# OSO-MISC-21-005_SAML22_Feather.net
KiCad netlist of a schematic drawn in EAGLE
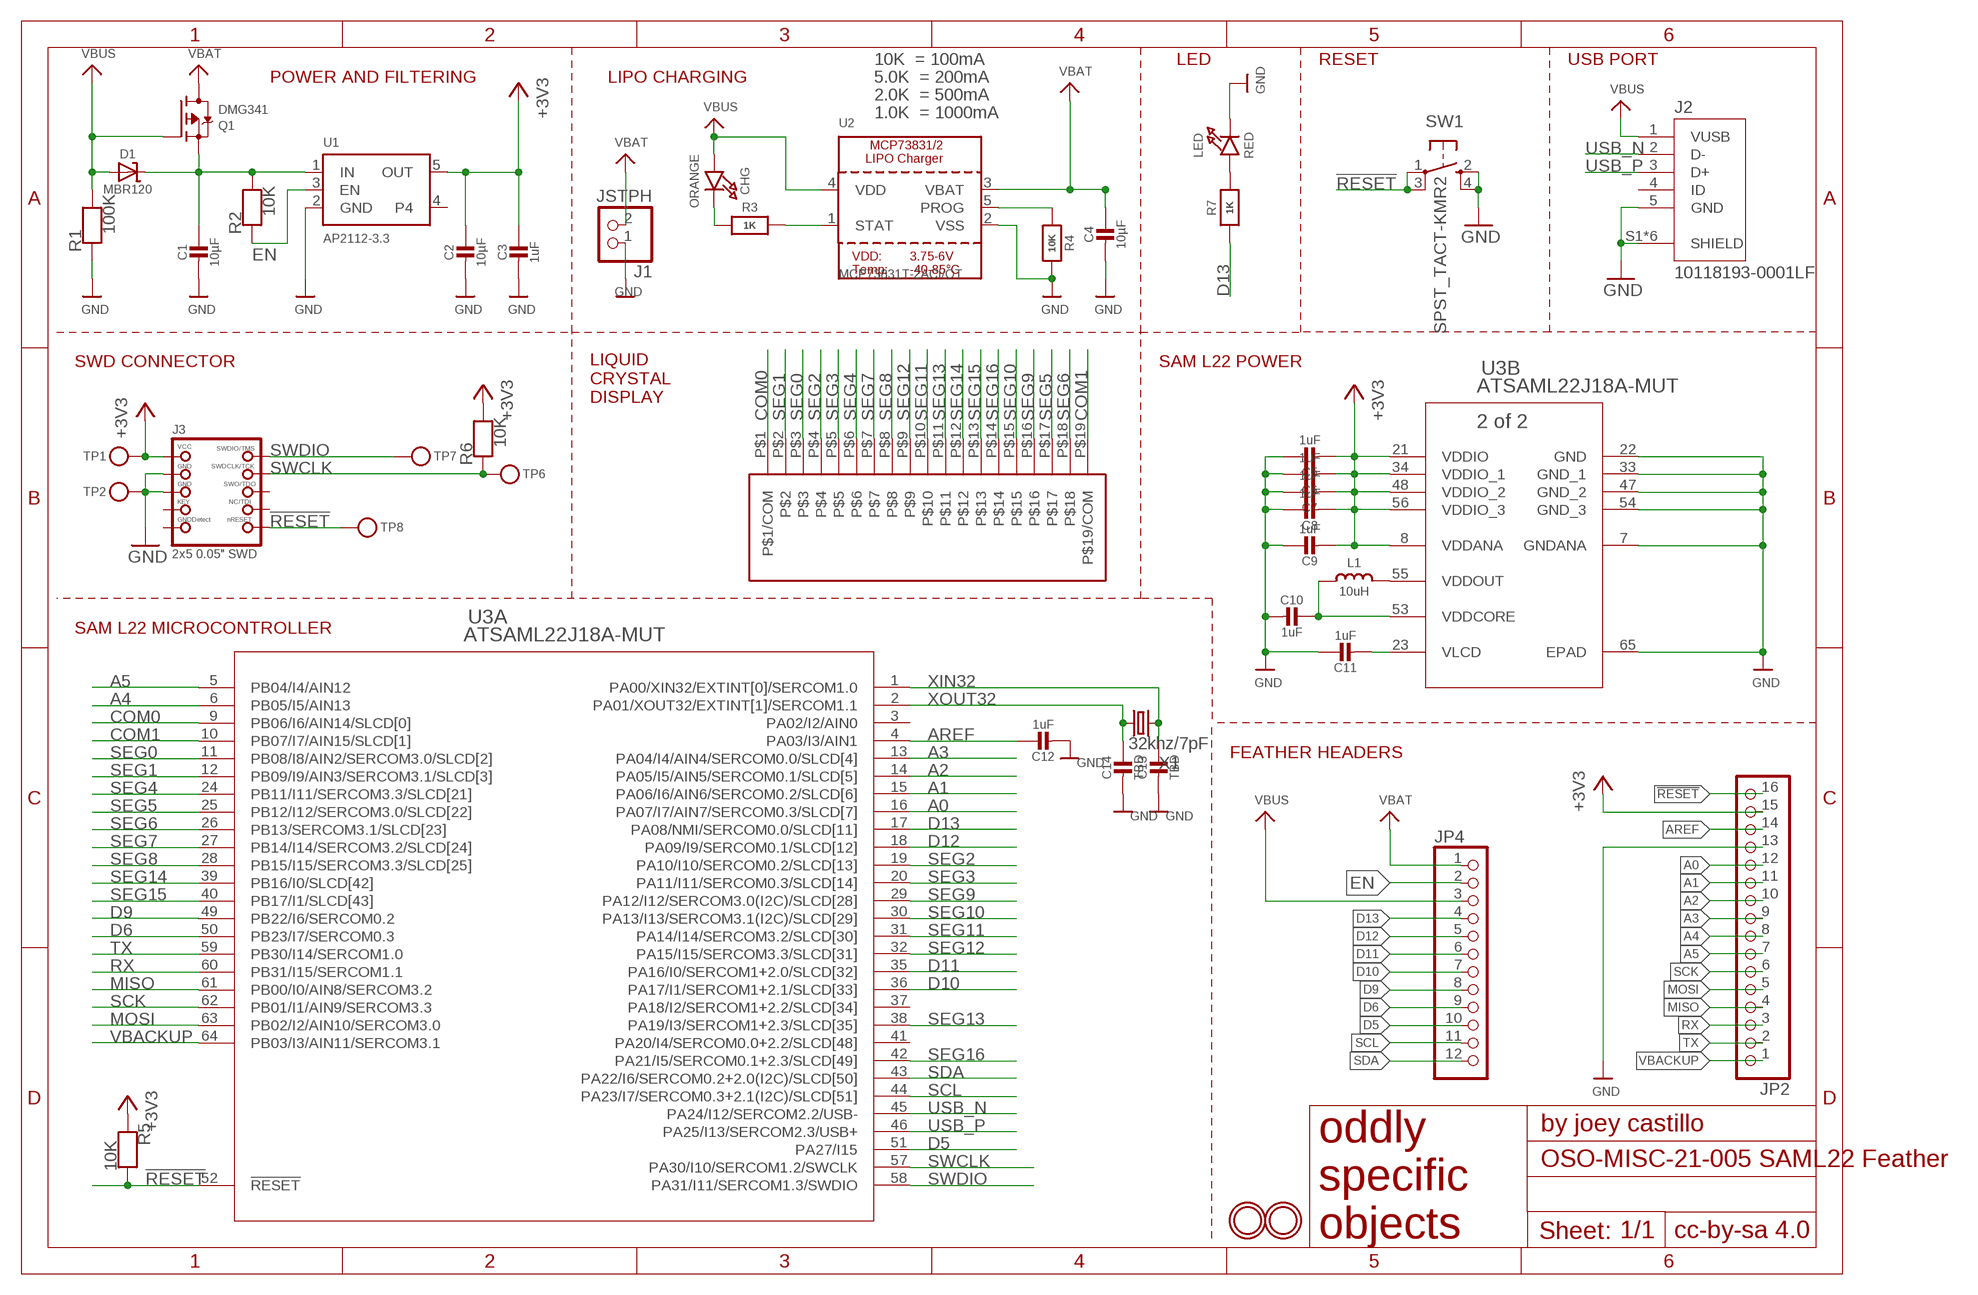
[diagram p0: schematic, sheet 1]

(export (version "E")
  (design (tool "Eeschema 10.0.6"))
  (components
    (comp (ref "C1")
      (value "10µF")
      (footprint "eagle-import:0805-NO")
      (libsource (lib "eagle-import") (part "CAP_CERAMIC0805-NOOUTLINE"))
    )
    (comp (ref "C2")
      (value "10µF")
      (footprint "eagle-import:0805-NO")
      (libsource (lib "eagle-import") (part "CAP_CERAMIC0805-NOOUTLINE"))
    )
    (comp (ref "C3")
      (value "1uF")
      (footprint "eagle-import:0603-NO")
      (libsource (lib "eagle-import") (part "CAP_CERAMIC0603_NO"))
    )
    (comp (ref "C4")
      (value "10µF")
      (footprint "eagle-import:0805-NO")
      (libsource (lib "eagle-import") (part "CAP_CERAMIC0805-NOOUTLINE"))
    )
    (comp (ref "C5")
      (value "1uF")
      (footprint "eagle-import:_0603MP")
      (libsource (lib "eagle-import") (part "CAP_CERAMIC_0603MP"))
    )
    (comp (ref "C6")
      (value "1uF")
      (footprint "eagle-import:0603-NO")
      (libsource (lib "eagle-import") (part "CAP_CERAMIC0603_NO"))
    )
    (comp (ref "C7")
      (value "1uF")
      (footprint "eagle-import:0603-NO")
      (libsource (lib "eagle-import") (part "CAP_CERAMIC0603_NO"))
    )
    (comp (ref "C8")
      (value "1uF")
      (footprint "eagle-import:0603-NO")
      (libsource (lib "eagle-import") (part "CAP_CERAMIC0603_NO"))
    )
    (comp (ref "C9")
      (value "1uF")
      (footprint "eagle-import:0603-NO")
      (libsource (lib "eagle-import") (part "CAP_CERAMIC0603_NO"))
    )
    (comp (ref "C10")
      (value "1uF")
      (footprint "eagle-import:_0603MP")
      (libsource (lib "eagle-import") (part "CAP_CERAMIC_0603MP"))
    )
    (comp (ref "C11")
      (value "1uF")
      (footprint "eagle-import:_0603MP")
      (libsource (lib "eagle-import") (part "CAP_CERAMIC_0603MP"))
    )
    (comp (ref "C12")
      (value "1uF")
      (footprint "eagle-import:0603-NO")
      (libsource (lib "eagle-import") (part "CAP_CERAMIC0603_NO"))
    )
    (comp (ref "C13")
      (value "TBD")
      (footprint "eagle-import:_0603MP")
      (libsource (lib "eagle-import") (part "CAP_CERAMIC_0603MP"))
    )
    (comp (ref "C14")
      (value "TBD")
      (footprint "eagle-import:_0603MP")
      (libsource (lib "eagle-import") (part "CAP_CERAMIC_0603MP"))
    )
    (comp (ref "CHG")
      (value "ORANGE")
      (footprint "eagle-import:CHIPLED_0805_NOOUTLINE")
      (libsource (lib "eagle-import") (part "LED0805_NOOUTLINE"))
    )
    (comp (ref "D1")
      (value "MBR120")
      (footprint "eagle-import:SOD-123")
      (libsource (lib "eagle-import") (part "DIODE-SCHOTTKYSOD-123"))
    )
    (comp (ref "J1")
      (value "JSTPH")
      (footprint "eagle-import:JSTPH2")
      (libsource (lib "eagle-import") (part "CON_JST_PH_2PIN"))
    )
    (comp (ref "J2")
      (value "10118193-0001LF")
      (footprint "eagle-import:FCI_10118193-0001LF")
      (fields (field (name "DIGI-KEY_PART_NUMBER") "609-4616-1-ND") (field (name "MF") "Amphenol ICC"))
      (libsource (lib "eagle-import") (part "10118193-0001LF"))
    )
    (comp (ref "J3")
      (value "2x5 0.05\" SWD")
      (footprint "eagle-import:2X05_1.27MM_BOX_NOPOSTS")
      (libsource (lib "eagle-import") (part "JTAG-CORTEXBOX"))
    )
    (comp (ref "JP2")
      (value "HEADER-1X16_MIN")
      (footprint "eagle-import:1X16_ROUND_MIN")
      (libsource (lib "eagle-import") (part "HEADER-1X16_MIN"))
    )
    (comp (ref "JP4")
      (value "HEADER-1X12_MIN")
      (footprint "eagle-import:1X12_ROUND_MIN")
      (libsource (lib "eagle-import") (part "HEADER-1X12_MIN"))
    )
    (comp (ref "L1")
      (value "10uH")
      (footprint "eagle-import:MICROBUILDER__0805MP")
      (libsource (lib "eagle-import") (part "MICROBUILDER_INDUCTOR_0805MP"))
    )
    (comp (ref "LED")
      (value "RED")
      (footprint "eagle-import:CHIPLED_0805_NOOUTLINE")
      (libsource (lib "eagle-import") (part "LED0805_NOOUTLINE"))
    )
    (comp (ref "Q1")
      (value "DMG341")
      (footprint "eagle-import:SOT23-R")
      (libsource (lib "eagle-import") (part "MOSFET-P"))
    )
    (comp (ref "R1")
      (value "100K")
      (footprint "eagle-import:0603-NO")
      (libsource (lib "eagle-import") (part "RESISTOR_0603_NOOUT"))
    )
    (comp (ref "R2")
      (value "10K")
      (footprint "eagle-import:0603-NO")
      (libsource (lib "eagle-import") (part "RESISTOR_0603_NOOUT"))
    )
    (comp (ref "R3")
      (value "1K")
      (footprint "eagle-import:0603-NO")
      (libsource (lib "eagle-import") (part "RESISTOR_0603_NOOUT"))
    )
    (comp (ref "R4")
      (value "10K")
      (footprint "eagle-import:0603-NO")
      (libsource (lib "eagle-import") (part "RESISTOR_0603_NOOUT"))
    )
    (comp (ref "R5")
      (value "10K")
      (footprint "eagle-import:0603-NO")
      (libsource (lib "eagle-import") (part "RESISTOR_0603_NOOUT"))
    )
    (comp (ref "R6")
      (value "10K")
      (footprint "eagle-import:0603-NO")
      (libsource (lib "eagle-import") (part "RESISTOR_0603_NOOUT"))
    )
    (comp (ref "R7")
      (value "1K")
      (footprint "eagle-import:0603-NO")
      (libsource (lib "eagle-import") (part "RESISTOR_0603_NOOUT"))
    )
    (comp (ref "SW1")
      (value "SPST_TACT-KMR2")
      (footprint "eagle-import:KMR2")
      (libsource (lib "eagle-import") (part "SPST_TACT-KMR2"))
    )
    (comp (ref "TP1")
      (value "TESTPOINTROUND2MMNO")
      (footprint "eagle-import:TESTPOINT_ROUND_2MM_NO")
      (libsource (lib "eagle-import") (part "TESTPOINTROUND2MMNO"))
    )
    (comp (ref "TP2")
      (value "TESTPOINTROUND2MMNO")
      (footprint "eagle-import:TESTPOINT_ROUND_2MM_NO")
      (libsource (lib "eagle-import") (part "TESTPOINTROUND2MMNO"))
    )
    (comp (ref "TP6")
      (value "TESTPOINTROUND2MMNO")
      (footprint "eagle-import:TESTPOINT_ROUND_2MM_NO")
      (libsource (lib "eagle-import") (part "TESTPOINTROUND2MMNO"))
    )
    (comp (ref "TP7")
      (value "TESTPOINTROUND2MMNO")
      (footprint "eagle-import:TESTPOINT_ROUND_2MM_NO")
      (libsource (lib "eagle-import") (part "TESTPOINTROUND2MMNO"))
    )
    (comp (ref "TP8")
      (value "TESTPOINTROUND2MMNO")
      (footprint "eagle-import:TESTPOINT_ROUND_2MM_NO")
      (libsource (lib "eagle-import") (part "TESTPOINTROUND2MMNO"))
    )
    (comp (ref "U$6")
      (value "OD-372")
      (footprint "eagle-import:OD-372")
      (libsource (lib "eagle-import") (part "OD-372"))
    )
    (comp (ref "U$31")
      (value "MOUNTINGHOLE2.5")
      (footprint "eagle-import:MOUNTINGHOLE_2.5_PLATED")
      (libsource (lib "eagle-import") (part "MOUNTINGHOLE2.5"))
    )
    (comp (ref "U$32")
      (value "MOUNTINGHOLE2.5")
      (footprint "eagle-import:MOUNTINGHOLE_2.5_PLATED")
      (libsource (lib "eagle-import") (part "MOUNTINGHOLE2.5"))
    )
    (comp (ref "U1")
      (value "AP2112-3.3")
      (footprint "eagle-import:SOT23-5")
      (libsource (lib "eagle-import") (part "VREG_SOT23-5"))
    )
    (comp (ref "U2")
      (value "MCP73831T-2ACI/OT")
      (footprint "eagle-import:SOT23-5")
      (libsource (lib "eagle-import") (part "MCP73831/2"))
    )
    (comp (ref "U3")
      (value "ATSAML22J18A-MUT")
      (footprint "eagle-import:QFN64_9X9MC_MCH")
      (fields (field (name "COPYRIGHT") "Copyright (C) 2018 Accelerated Designs. All rights reserved"))
      (libsource (lib "eagle-import") (part "ATSAML22J18A-MUT"))
    )
    (comp (ref "X1")
      (value "32khz/7pF")
      (footprint "eagle-import:XTAL-7015")
      (libsource (lib "eagle-import") (part "CRYSTAL7015"))
    )
  )
  (nets
    (net (code "1") (name "+3V3") (class "Default")
      (node (ref "C2") (pin "1") (pinfunction "1_1") (pintype "passive"))
      (node (ref "C3") (pin "1") (pinfunction "1_1") (pintype "passive"))
      (node (ref "C5") (pin "2") (pinfunction "2_2") (pintype "passive"))
      (node (ref "C6") (pin "2") (pinfunction "2_2") (pintype "passive"))
      (node (ref "C7") (pin "2") (pinfunction "2_2") (pintype "passive"))
      (node (ref "C8") (pin "2") (pinfunction "2_2") (pintype "passive"))
      (node (ref "C9") (pin "2") (pinfunction "2_2") (pintype "passive"))
      (node (ref "J3") (pin "1") (pinfunction "VCC_1") (pintype "power_in"))
      (node (ref "JP2") (pin "15") (pinfunction "15_15") (pintype "passive"))
      (node (ref "R5") (pin "1") (pinfunction "1_1") (pintype "passive"))
      (node (ref "R6") (pin "2") (pinfunction "2_2") (pintype "passive"))
      (node (ref "TP1") (pin "P$1") (pinfunction "P$1_P$1") (pintype "bidirectional"))
      (node (ref "U1") (pin "5") (pinfunction "OUT_5") (pintype "power_in"))
      (node (ref "U3") (pin "21") (pinfunction "VDDIO_21") (pintype "power_in"))
      (node (ref "U3") (pin "34") (pinfunction "VDDIO_1_34") (pintype "power_in"))
      (node (ref "U3") (pin "48") (pinfunction "VDDIO_2_48") (pintype "power_in"))
      (node (ref "U3") (pin "56") (pinfunction "VDDIO_3_56") (pintype "power_in"))
      (node (ref "U3") (pin "8") (pinfunction "VDDANA_8") (pintype "power_in"))
    )
    (net (code "2") (name "/COM0") (class "Default")
      (node (ref "U$6") (pin "P$1") (pinfunction "P$1/COM_P$1") (pintype "bidirectional"))
      (node (ref "U3") (pin "9") (pinfunction "PB06/I6/AIN14/SLCD[0]_9") (pintype "bidirectional"))
    )
    (net (code "3") (name "/COM1") (class "Default")
      (node (ref "U$6") (pin "P$19") (pinfunction "P$19/COM_P$19") (pintype "bidirectional"))
      (node (ref "U3") (pin "10") (pinfunction "PB07/I7/AIN15/SLCD[1]_10") (pintype "bidirectional"))
    )
    (net (code "4") (name "/SEG0") (class "Default")
      (node (ref "U$6") (pin "P$3") (pinfunction "P$3_P$3") (pintype "bidirectional"))
      (node (ref "U3") (pin "11") (pinfunction "PB08/I8/AIN2/SERCOM3.0/SLCD[2]_11") (pintype "bidirectional"))
    )
    (net (code "5") (name "/SEG1") (class "Default")
      (node (ref "U$6") (pin "P$2") (pinfunction "P$2_P$2") (pintype "bidirectional"))
      (node (ref "U3") (pin "12") (pinfunction "PB09/I9/AIN3/SERCOM3.1/SLCD[3]_12") (pintype "bidirectional"))
    )
    (net (code "6") (name "/SEG2") (class "Default")
      (node (ref "U$6") (pin "P$4") (pinfunction "P$4_P$4") (pintype "bidirectional"))
      (node (ref "U3") (pin "19") (pinfunction "PA10/I10/SERCOM0.2/SLCD[13]_19") (pintype "bidirectional"))
    )
    (net (code "7") (name "/SEG3") (class "Default")
      (node (ref "U$6") (pin "P$5") (pinfunction "P$5_P$5") (pintype "bidirectional"))
      (node (ref "U3") (pin "20") (pinfunction "PA11/I11/SERCOM0.3/SLCD[14]_20") (pintype "bidirectional"))
    )
    (net (code "8") (name "/SEG4") (class "Default")
      (node (ref "U$6") (pin "P$6") (pinfunction "P$6_P$6") (pintype "bidirectional"))
      (node (ref "U3") (pin "24") (pinfunction "PB11/I11/SERCOM3.3/SLCD[21]_24") (pintype "bidirectional"))
    )
    (net (code "9") (name "/SEG5") (class "Default")
      (node (ref "U$6") (pin "P$17") (pinfunction "P$17_P$17") (pintype "bidirectional"))
      (node (ref "U3") (pin "25") (pinfunction "PB12/I12/SERCOM3.0/SLCD[22]_25") (pintype "bidirectional"))
    )
    (net (code "10") (name "/SEG6") (class "Default")
      (node (ref "U$6") (pin "P$18") (pinfunction "P$18_P$18") (pintype "bidirectional"))
      (node (ref "U3") (pin "26") (pinfunction "PB13/SERCOM3.1/SLCD[23]_26") (pintype "bidirectional"))
    )
    (net (code "11") (name "/SEG7") (class "Default")
      (node (ref "U$6") (pin "P$7") (pinfunction "P$7_P$7") (pintype "bidirectional"))
      (node (ref "U3") (pin "27") (pinfunction "PB14/I14/SERCOM3.2/SLCD[24]_27") (pintype "bidirectional"))
    )
    (net (code "12") (name "/SEG8") (class "Default")
      (node (ref "U$6") (pin "P$8") (pinfunction "P$8_P$8") (pintype "bidirectional"))
      (node (ref "U3") (pin "28") (pinfunction "PB15/I15/SERCOM3.3/SLCD[25]_28") (pintype "bidirectional"))
    )
    (net (code "13") (name "/SEG9") (class "Default")
      (node (ref "U$6") (pin "P$16") (pinfunction "P$16_P$16") (pintype "bidirectional"))
      (node (ref "U3") (pin "29") (pinfunction "PA12/I12/SERCOM3.0(I2C)/SLCD[28]_29") (pintype "bidirectional"))
    )
    (net (code "14") (name "/SEG10") (class "Default")
      (node (ref "U$6") (pin "P$15") (pinfunction "P$15_P$15") (pintype "bidirectional"))
      (node (ref "U3") (pin "30") (pinfunction "PA13/I13/SERCOM3.1(I2C)/SLCD[29]_30") (pintype "bidirectional"))
    )
    (net (code "15") (name "/SEG11") (class "Default")
      (node (ref "U$6") (pin "P$10") (pinfunction "P$10_P$10") (pintype "bidirectional"))
      (node (ref "U3") (pin "31") (pinfunction "PA14/I14/SERCOM3.2/SLCD[30]_31") (pintype "bidirectional"))
    )
    (net (code "16") (name "/SEG12") (class "Default")
      (node (ref "U$6") (pin "P$9") (pinfunction "P$9_P$9") (pintype "bidirectional"))
      (node (ref "U3") (pin "32") (pinfunction "PA15/I15/SERCOM3.3/SLCD[31]_32") (pintype "bidirectional"))
    )
    (net (code "17") (name "/SEG13") (class "Default")
      (node (ref "U$6") (pin "P$11") (pinfunction "P$11_P$11") (pintype "bidirectional"))
      (node (ref "U3") (pin "38") (pinfunction "PA19/I3/SERCOM1+2.3/SLCD[35]_38") (pintype "bidirectional"))
    )
    (net (code "18") (name "/SEG14") (class "Default")
      (node (ref "U$6") (pin "P$12") (pinfunction "P$12_P$12") (pintype "bidirectional"))
      (node (ref "U3") (pin "39") (pinfunction "PB16/I0/SLCD[42]_39") (pintype "bidirectional"))
    )
    (net (code "19") (name "/SEG15") (class "Default")
      (node (ref "U$6") (pin "P$13") (pinfunction "P$13_P$13") (pintype "bidirectional"))
      (node (ref "U3") (pin "40") (pinfunction "PB17/I1/SLCD[43]_40") (pintype "bidirectional"))
    )
    (net (code "20") (name "/SEG16") (class "Default")
      (node (ref "U$6") (pin "P$14") (pinfunction "P$14_P$14") (pintype "bidirectional"))
      (node (ref "U3") (pin "42") (pinfunction "PA21/I5/SERCOM0.1+2.3/SLCD[49]_42") (pintype "bidirectional"))
    )
    (net (code "21") (name "/SWCLK") (class "Default")
      (node (ref "J3") (pin "4") (pinfunction "SWDCLK_4") (pintype "bidirectional"))
      (node (ref "R6") (pin "1") (pinfunction "1_1") (pintype "passive"))
      (node (ref "TP6") (pin "P$1") (pinfunction "P$1_P$1") (pintype "bidirectional"))
      (node (ref "U3") (pin "57") (pinfunction "PA30/I10/SERCOM1.2/SWCLK_57") (pintype "bidirectional"))
    )
    (net (code "22") (name "/SWDIO") (class "Default")
      (node (ref "J3") (pin "2") (pinfunction "SWDIO_2") (pintype "bidirectional"))
      (node (ref "TP7") (pin "P$1") (pinfunction "P$1_P$1") (pintype "bidirectional"))
      (node (ref "U3") (pin "58") (pinfunction "PA31/I11/SERCOM1.3/SWDIO_58") (pintype "bidirectional"))
    )
    (net (code "23") (name "/USB_N") (class "Default")
      (node (ref "J2") (pin "2") (pinfunction "D-_2") (pintype "passive"))
      (node (ref "U3") (pin "45") (pinfunction "PA24/I12/SERCOM2.2/USB-_45") (pintype "bidirectional"))
    )
    (net (code "24") (name "/USB_P") (class "Default")
      (node (ref "J2") (pin "3") (pinfunction "D+_3") (pintype "passive"))
      (node (ref "U3") (pin "46") (pinfunction "PA25/I13/SERCOM2.3/USB+_46") (pintype "bidirectional"))
    )
    (net (code "25") (name "/XIN32") (class "Default")
      (node (ref "C13") (pin "1") (pinfunction "1_1") (pintype "passive"))
      (node (ref "U3") (pin "1") (pinfunction "PA00/XIN32/EXTINT[0]/SERCOM1.0_1") (pintype "bidirectional"))
      (node (ref "X1") (pin "4") (pinfunction "2_4") (pintype "passive"))
    )
    (net (code "26") (name "/XOUT32") (class "Default")
      (node (ref "C14") (pin "1") (pinfunction "1_1") (pintype "passive"))
      (node (ref "U3") (pin "2") (pinfunction "PA01/XOUT32/EXTINT[1]/SERCOM1.1_2") (pintype "bidirectional"))
      (node (ref "X1") (pin "1") (pinfunction "1_1") (pintype "passive"))
    )
    (net (code "27") (name "/~{RESET}") (class "Default")
      (node (ref "J3") (pin "10") (pinfunction "NRESET_10") (pintype "bidirectional"))
      (node (ref "JP2") (pin "16") (pinfunction "16_16") (pintype "passive"))
      (node (ref "R5") (pin "2") (pinfunction "2_2") (pintype "passive"))
      (node (ref "SW1") (pin "1") (pinfunction "P_1") (pintype "passive"))
      (node (ref "SW1") (pin "3") (pinfunction "P1_3") (pintype "passive"))
      (node (ref "TP8") (pin "P$1") (pinfunction "P$1_P$1") (pintype "bidirectional"))
      (node (ref "U3") (pin "52") (pinfunction "~{RESET}_52") (pintype "bidirectional"))
    )
    (net (code "28") (name "A0") (class "Default")
      (node (ref "JP2") (pin "12") (pinfunction "12_12") (pintype "passive"))
      (node (ref "U3") (pin "16") (pinfunction "PA07/I7/AIN7/SERCOM0.3/SLCD[7]_16") (pintype "bidirectional"))
    )
    (net (code "29") (name "A1") (class "Default")
      (node (ref "JP2") (pin "11") (pinfunction "11_11") (pintype "passive"))
      (node (ref "U3") (pin "15") (pinfunction "PA06/I6/AIN6/SERCOM0.2/SLCD[6]_15") (pintype "bidirectional"))
    )
    (net (code "30") (name "A2") (class "Default")
      (node (ref "JP2") (pin "10") (pinfunction "10_10") (pintype "passive"))
      (node (ref "U3") (pin "14") (pinfunction "PA05/I5/AIN5/SERCOM0.1/SLCD[5]_14") (pintype "bidirectional"))
    )
    (net (code "31") (name "A3") (class "Default")
      (node (ref "JP2") (pin "9") (pinfunction "9_9") (pintype "passive"))
      (node (ref "U3") (pin "13") (pinfunction "PA04/I4/AIN4/SERCOM0.0/SLCD[4]_13") (pintype "bidirectional"))
    )
    (net (code "32") (name "A4") (class "Default")
      (node (ref "JP2") (pin "8") (pinfunction "8_8") (pintype "passive"))
      (node (ref "U3") (pin "6") (pinfunction "PB05/I5/AIN13_6") (pintype "bidirectional"))
    )
    (net (code "33") (name "A5") (class "Default")
      (node (ref "JP2") (pin "7") (pinfunction "7_7") (pintype "passive"))
      (node (ref "U3") (pin "5") (pinfunction "PB04/I4/AIN12_5") (pintype "bidirectional"))
    )
    (net (code "34") (name "AREF") (class "Default")
      (node (ref "C12") (pin "1") (pinfunction "1_1") (pintype "passive"))
      (node (ref "JP2") (pin "14") (pinfunction "14_14") (pintype "passive"))
      (node (ref "U3") (pin "4") (pinfunction "PA03/I3/AIN1_4") (pintype "bidirectional"))
    )
    (net (code "35") (name "D5") (class "Default")
      (node (ref "JP4") (pin "10") (pinfunction "10_10") (pintype "passive"))
      (node (ref "U3") (pin "51") (pinfunction "PA27/I15_51") (pintype "bidirectional"))
    )
    (net (code "36") (name "D6") (class "Default")
      (node (ref "JP4") (pin "9") (pinfunction "9_9") (pintype "passive"))
      (node (ref "U3") (pin "50") (pinfunction "PB23/I7/SERCOM0.3_50") (pintype "bidirectional"))
    )
    (net (code "37") (name "D9") (class "Default")
      (node (ref "JP4") (pin "8") (pinfunction "8_8") (pintype "passive"))
      (node (ref "U3") (pin "49") (pinfunction "PB22/I6/SERCOM0.2_49") (pintype "bidirectional"))
    )
    (net (code "38") (name "D10") (class "Default")
      (node (ref "JP4") (pin "7") (pinfunction "7_7") (pintype "passive"))
      (node (ref "U3") (pin "36") (pinfunction "PA17/I1/SERCOM1+2.1/SLCD[33]_36") (pintype "bidirectional"))
    )
    (net (code "39") (name "D11") (class "Default")
      (node (ref "JP4") (pin "6") (pinfunction "6_6") (pintype "passive"))
      (node (ref "U3") (pin "35") (pinfunction "PA16/I0/SERCOM1+2.0/SLCD[32]_35") (pintype "bidirectional"))
    )
    (net (code "40") (name "D12") (class "Default")
      (node (ref "JP4") (pin "5") (pinfunction "5_5") (pintype "passive"))
      (node (ref "U3") (pin "18") (pinfunction "PA09/I9/SERCOM0.1/SLCD[12]_18") (pintype "bidirectional"))
    )
    (net (code "41") (name "D13") (class "Default")
      (node (ref "JP4") (pin "4") (pinfunction "4_4") (pintype "passive"))
      (node (ref "R7") (pin "1") (pinfunction "1_1") (pintype "passive"))
      (node (ref "U3") (pin "17") (pinfunction "PA08/NMI/SERCOM0.0/SLCD[11]_17") (pintype "bidirectional"))
    )
    (net (code "42") (name "EN") (class "Default")
      (node (ref "JP4") (pin "2") (pinfunction "2_2") (pintype "passive"))
      (node (ref "R2") (pin "1") (pinfunction "1_1") (pintype "passive"))
      (node (ref "U1") (pin "3") (pinfunction "EN_3") (pintype "input"))
    )
    (net (code "43") (name "GND") (class "Default")
      (node (ref "C1") (pin "2") (pinfunction "2_2") (pintype "passive"))
      (node (ref "C10") (pin "2") (pinfunction "2_2") (pintype "passive"))
      (node (ref "C11") (pin "1") (pinfunction "1_1") (pintype "passive"))
      (node (ref "C12") (pin "2") (pinfunction "2_2") (pintype "passive"))
      (node (ref "C13") (pin "2") (pinfunction "2_2") (pintype "passive"))
      (node (ref "C14") (pin "2") (pinfunction "2_2") (pintype "passive"))
      (node (ref "C2") (pin "2") (pinfunction "2_2") (pintype "passive"))
      (node (ref "C3") (pin "2") (pinfunction "2_2") (pintype "passive"))
      (node (ref "C4") (pin "2") (pinfunction "2_2") (pintype "passive"))
      (node (ref "C5") (pin "1") (pinfunction "1_1") (pintype "passive"))
      (node (ref "C6") (pin "1") (pinfunction "1_1") (pintype "passive"))
      (node (ref "C7") (pin "1") (pinfunction "1_1") (pintype "passive"))
      (node (ref "C8") (pin "1") (pinfunction "1_1") (pintype "passive"))
      (node (ref "C9") (pin "1") (pinfunction "1_1") (pintype "passive"))
      (node (ref "J1") (pin "1") (pinfunction "1_1") (pintype "passive"))
      (node (ref "J2") (pin "5") (pinfunction "GND_5") (pintype "passive"))
      (node (ref "J2") (pin "S1") (pinfunction "SHIELD_S1") (pintype "passive"))
      (node (ref "J2") (pin "S2") (pinfunction "SHIELD_S2") (pintype "passive"))
      (node (ref "J2") (pin "S3") (pinfunction "SHIELD_S3") (pintype "passive"))
      (node (ref "J2") (pin "S4") (pinfunction "SHIELD_S4") (pintype "passive"))
      (node (ref "J2") (pin "S5") (pinfunction "SHIELD_S5") (pintype "passive"))
      (node (ref "J2") (pin "S6") (pinfunction "SHIELD_S6") (pintype "passive"))
      (node (ref "J3") (pin "3") (pinfunction "GND_3") (pintype "power_in"))
      (node (ref "J3") (pin "5") (pinfunction "GND_5") (pintype "power_in"))
      (node (ref "JP2") (pin "13") (pinfunction "13_13") (pintype "passive"))
      (node (ref "LED") (pin "C") (pinfunction "C_C") (pintype "passive"))
      (node (ref "R1") (pin "1") (pinfunction "1_1") (pintype "passive"))
      (node (ref "R4") (pin "2") (pinfunction "2_2") (pintype "passive"))
      (node (ref "SW1") (pin "2") (pinfunction "S_2") (pintype "passive"))
      (node (ref "SW1") (pin "4") (pinfunction "S1_4") (pintype "passive"))
      (node (ref "TP2") (pin "P$1") (pinfunction "P$1_P$1") (pintype "bidirectional"))
      (node (ref "U1") (pin "2") (pinfunction "GND_2") (pintype "power_in"))
      (node (ref "U2") (pin "2") (pinfunction "VSS_2") (pintype "power_in"))
      (node (ref "U3") (pin "22") (pinfunction "GND_22") (pintype "passive"))
      (node (ref "U3") (pin "33") (pinfunction "GND_1_33") (pintype "passive"))
      (node (ref "U3") (pin "47") (pinfunction "GND_2_47") (pintype "passive"))
      (node (ref "U3") (pin "54") (pinfunction "GND_3_54") (pintype "passive"))
      (node (ref "U3") (pin "65") (pinfunction "EPAD_65") (pintype "passive"))
      (node (ref "U3") (pin "7") (pinfunction "GNDANA_7") (pintype "passive"))
    )
    (net (code "44") (name "MISO") (class "Default")
      (node (ref "JP2") (pin "4") (pinfunction "4_4") (pintype "passive"))
      (node (ref "U3") (pin "61") (pinfunction "PB00/I0/AIN8/SERCOM3.2_61") (pintype "bidirectional"))
    )
    (net (code "45") (name "MOSI") (class "Default")
      (node (ref "JP2") (pin "5") (pinfunction "5_5") (pintype "passive"))
      (node (ref "U3") (pin "63") (pinfunction "PB02/I2/AIN10/SERCOM3.0_63") (pintype "bidirectional"))
    )
    (net (code "46") (name "Net-(CHG-PadC)") (class "Default")
      (node (ref "CHG") (pin "C") (pinfunction "C_C") (pintype "passive"))
      (node (ref "R3") (pin "1") (pinfunction "1_1") (pintype "passive"))
    )
    (net (code "47") (name "Net-(LED-PadA)") (class "Default")
      (node (ref "LED") (pin "A") (pinfunction "A_A") (pintype "passive"))
      (node (ref "R7") (pin "2") (pinfunction "2_2") (pintype "passive"))
    )
    (net (code "48") (name "Net-(Q1-S)") (class "Default")
      (node (ref "C1") (pin "1") (pinfunction "1_1") (pintype "passive"))
      (node (ref "D1") (pin "C") (pinfunction "C_C") (pintype "passive"))
      (node (ref "Q1") (pin "2") (pinfunction "S_2") (pintype "passive"))
      (node (ref "R2") (pin "2") (pinfunction "2_2") (pintype "passive"))
      (node (ref "U1") (pin "1") (pinfunction "IN_1") (pintype "power_in"))
    )
    (net (code "49") (name "Net-(U2-PROG)") (class "Default")
      (node (ref "R4") (pin "1") (pinfunction "1_1") (pintype "passive"))
      (node (ref "U2") (pin "5") (pinfunction "PROG_5") (pintype "input"))
    )
    (net (code "50") (name "Net-(U2-STAT)") (class "Default")
      (node (ref "R3") (pin "2") (pinfunction "2_2") (pintype "passive"))
      (node (ref "U2") (pin "1") (pinfunction "STAT_1") (pintype "output"))
    )
    (net (code "51") (name "Net-(U3B-VDDCORE)") (class "Default")
      (node (ref "C10") (pin "1") (pinfunction "1_1") (pintype "passive"))
      (node (ref "L1") (pin "1") (pinfunction "1_1") (pintype "passive"))
      (node (ref "U3") (pin "53") (pinfunction "VDDCORE_53") (pintype "power_in"))
    )
    (net (code "52") (name "Net-(U3B-VDDOUT)") (class "Default")
      (node (ref "L1") (pin "2") (pinfunction "2_2") (pintype "passive"))
      (node (ref "U3") (pin "55") (pinfunction "VDDOUT_55") (pintype "output"))
    )
    (net (code "53") (name "Net-(U3B-VLCD)") (class "Default")
      (node (ref "C11") (pin "2") (pinfunction "2_2") (pintype "passive"))
      (node (ref "U3") (pin "23") (pinfunction "VLCD_23") (pintype "passive"))
    )
    (net (code "54") (name "RX") (class "Default")
      (node (ref "JP2") (pin "3") (pinfunction "3_3") (pintype "passive"))
      (node (ref "U3") (pin "60") (pinfunction "PB31/I15/SERCOM1.1_60") (pintype "bidirectional"))
    )
    (net (code "55") (name "SCK") (class "Default")
      (node (ref "JP2") (pin "6") (pinfunction "6_6") (pintype "passive"))
      (node (ref "U3") (pin "62") (pinfunction "PB01/I1/AIN9/SERCOM3.3_62") (pintype "bidirectional"))
    )
    (net (code "56") (name "SCL") (class "Default")
      (node (ref "JP4") (pin "11") (pinfunction "11_11") (pintype "passive"))
      (node (ref "U3") (pin "44") (pinfunction "PA23/I7/SERCOM0.3+2.1(I2C)/SLCD[51]_44") (pintype "bidirectional"))
    )
    (net (code "57") (name "SDA") (class "Default")
      (node (ref "JP4") (pin "12") (pinfunction "12_12") (pintype "passive"))
      (node (ref "U3") (pin "43") (pinfunction "PA22/I6/SERCOM0.2+2.0(I2C)/SLCD[50]_43") (pintype "bidirectional"))
    )
    (net (code "58") (name "TX") (class "Default")
      (node (ref "JP2") (pin "2") (pinfunction "2_2") (pintype "passive"))
      (node (ref "U3") (pin "59") (pinfunction "PB30/I14/SERCOM1.0_59") (pintype "bidirectional"))
    )
    (net (code "59") (name "VBACKUP") (class "Default")
      (node (ref "JP2") (pin "1") (pinfunction "1_1") (pintype "passive"))
      (node (ref "U3") (pin "64") (pinfunction "PB03/I3/AIN11/SERCOM3.1_64") (pintype "bidirectional"))
    )
    (net (code "60") (name "VBAT") (class "Default")
      (node (ref "C4") (pin "1") (pinfunction "1_1") (pintype "passive"))
      (node (ref "J1") (pin "2") (pinfunction "2_2") (pintype "passive"))
      (node (ref "JP4") (pin "1") (pinfunction "1_1") (pintype "passive"))
      (node (ref "Q1") (pin "3") (pinfunction "D_3") (pintype "passive"))
      (node (ref "U2") (pin "3") (pinfunction "VBAT_3") (pintype "power_in"))
    )
    (net (code "61") (name "VBUS") (class "Default")
      (node (ref "CHG") (pin "A") (pinfunction "A_A") (pintype "passive"))
      (node (ref "D1") (pin "A") (pinfunction "A_A") (pintype "passive"))
      (node (ref "J2") (pin "1") (pinfunction "VUSB_1") (pintype "passive"))
      (node (ref "JP4") (pin "3") (pinfunction "3_3") (pintype "passive"))
      (node (ref "Q1") (pin "1") (pinfunction "G_1") (pintype "passive"))
      (node (ref "R1") (pin "2") (pinfunction "2_2") (pintype "passive"))
      (node (ref "U2") (pin "4") (pinfunction "VDD_4") (pintype "power_in"))
    )
    (net (code "62") (name "unconnected-(J2-ID-Pad4)") (class "Default")
      (node (ref "J2") (pin "4") (pinfunction "ID_4") (pintype "passive"))
    )
    (net (code "63") (name "unconnected-(J3-GNDDETECT-Pad9)") (class "Default")
      (node (ref "J3") (pin "9") (pinfunction "GNDDETECT_9") (pintype "bidirectional"))
    )
    (net (code "64") (name "unconnected-(J3-KEY-Pad7)") (class "Default")
      (node (ref "J3") (pin "7") (pinfunction "KEY_7") (pintype "bidirectional"))
    )
    (net (code "65") (name "unconnected-(J3-SWO-Pad6)") (class "Default")
      (node (ref "J3") (pin "6") (pinfunction "SWO_6") (pintype "bidirectional"))
    )
    (net (code "66") (name "unconnected-(J3-TDI-Pad8)") (class "Default")
      (node (ref "J3") (pin "8") (pinfunction "TDI_8") (pintype "bidirectional"))
    )
    (net (code "67") (name "unconnected-(U1-P4-Pad4)") (class "Default")
      (node (ref "U1") (pin "4") (pinfunction "P4_4") (pintype "bidirectional"))
    )
    (net (code "68") (name "unconnected-(U3A-PA02{slash}I2{slash}AIN0-Pad3)") (class "Default")
      (node (ref "U3") (pin "3") (pinfunction "PA02/I2/AIN0_3") (pintype "bidirectional"))
    )
    (net (code "69") (name "unconnected-(U3A-PA18{slash}I2{slash}SERCOM1+2.2{slash}SLCD[34]-Pad37)") (class "Default")
      (node (ref "U3") (pin "37") (pinfunction "PA18/I2/SERCOM1+2.2/SLCD[34]_37") (pintype "bidirectional"))
    )
    (net (code "70") (name "unconnected-(U3A-PA20{slash}I4{slash}SERCOM0.0+2.2{slash}SLCD[48]-Pad41)") (class "Default")
      (node (ref "U3") (pin "41") (pinfunction "PA20/I4/SERCOM0.0+2.2/SLCD[48]_41") (pintype "bidirectional"))
    )
  )
)
